# CVSP1_2010.net
KiCad netlist of a schematic drawn in Altium Designer
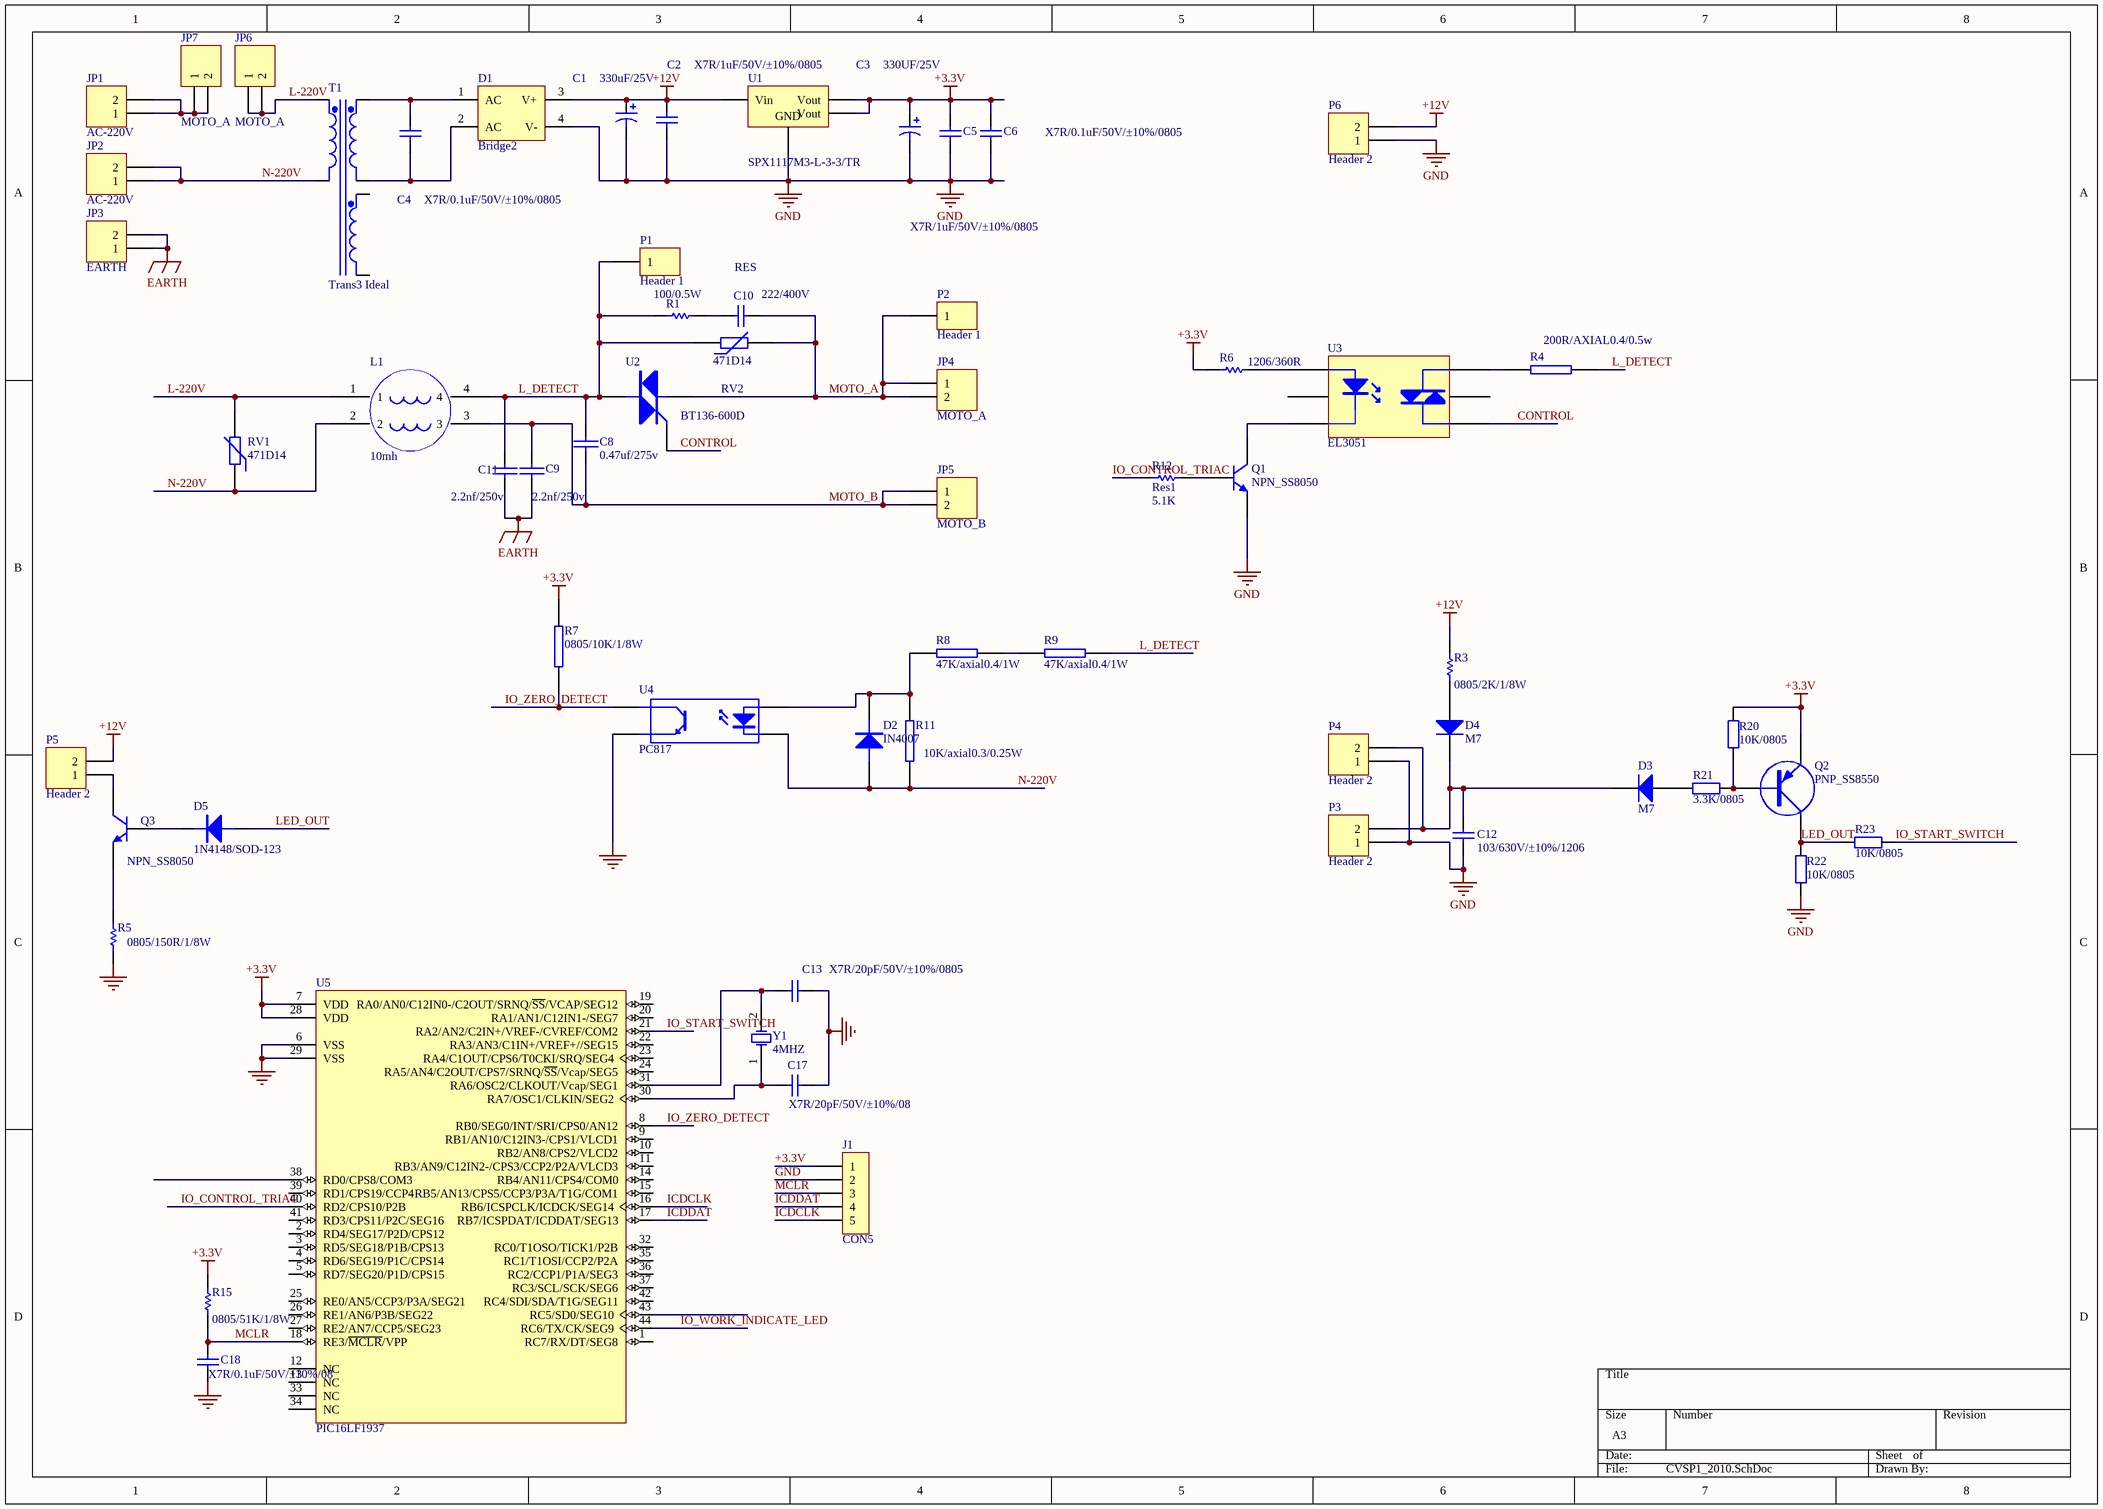
[diagram p0: CVSP1_2010.SchDoc]

(export (version "E")
  (design (tool "Eeschema 10.0.6"))
  (components
    (comp (ref "C1")
      (value "330uF/25V")
      (footprint "CAP/3.2mm*12mm*8mm")
      (description "Polarized Capacitor (Radial)")
      (fields (field (name "Comment") "Cap Pol1") (field (name "PUBLISHER") "Altium Limited"))
      (libsource (lib "Miscellaneous Devices") (part "Cap Pol1"))
    )
    (comp (ref "C2")
      (value "X7R/1uF/50V/±10%/0805")
      (footprint "0805C")
      (description "Capacitor")
      (fields (field (name "Comment") "Cap") (field (name "PUBLISHER") "Altium Limited"))
      (libsource (lib "Miscellaneous Devices") (part "Cap"))
    )
    (comp (ref "C3")
      (value "330UF/25V")
      (footprint "CAP/3.2mm*12mm*8mm")
      (description "Polarized Capacitor (Radial)")
      (fields (field (name "Comment") "Cap Pol1") (field (name "PUBLISHER") "Altium Limited"))
      (libsource (lib "Miscellaneous Devices") (part "Cap Pol1"))
    )
    (comp (ref "C4")
      (value "X7R/0.1uF/50V/±10%/0805")
      (footprint "0805C")
      (description "Capacitor")
      (fields (field (name "PUBLISHER") "Altium Limited"))
      (libsource (lib "Miscellaneous Devices") (part "Cap"))
    )
    (comp (ref "C5")
      (value "X7R/1uF/50V/±10%/0805")
      (footprint "0805C")
      (description "Capacitor")
      (fields (field (name "Comment") "0805/105/25V") (field (name "PUBLISHER") "Altium Limited"))
      (libsource (lib "Miscellaneous Devices") (part "Cap"))
    )
    (comp (ref "C6")
      (value "X7R/0.1uF/50V/±10%/0805")
      (footprint "0805C")
      (description "Capacitor")
      (fields (field (name "PUBLISHER") "Altium Limited"))
      (libsource (lib "Miscellaneous Devices") (part "Cap"))
    )
    (comp (ref "C8")
      (value "0.47uf/275v")
      (footprint "CAP/0.47U/250V")
      (description "Capacitor")
      (libsource (lib "*") (part "CAP"))
    )
    (comp (ref "C9")
      (value "2.2nf/250v")
      (footprint "CAP/1KV")
      (description "Capacitor")
      (libsource (lib "*") (part "CAP"))
    )
    (comp (ref "C10")
      (value "222/400V")
      (footprint "CAP/1KV")
      (description "Capacitor")
      (fields (field (name "Comment") "Cap") (field (name "PUBLISHER") "Altium Limited"))
      (libsource (lib "Miscellaneous Devices") (part "Cap"))
    )
    (comp (ref "C11")
      (value "2.2nf/250v")
      (footprint "CAP/1KV")
      (description "Capacitor")
      (libsource (lib "*") (part "CAP"))
    )
    (comp (ref "C12")
      (value "103/630V/±10%/1206")
      (footprint "0805C")
      (description "Capacitor")
      (fields (field (name "Comment") "Cap") (field (name "PUBLISHER") "Altium Limited"))
      (libsource (lib "Miscellaneous Devices") (part "Cap"))
    )
    (comp (ref "C13")
      (value "X7R/20pF/50V/±10%/0805")
      (footprint "0805C")
      (description "Capacitor")
      (fields (field (name "Comment") "Cap") (field (name "PUBLISHER") "Altium Limited"))
      (libsource (lib "Miscellaneous Devices") (part "Cap"))
    )
    (comp (ref "C17")
      (value "X7R/20pF/50V/±10%/08")
      (footprint "0805C")
      (description "Capacitor")
      (fields (field (name "Comment") "Cap") (field (name "PUBLISHER") "Altium Limited"))
      (libsource (lib "Miscellaneous Devices") (part "Cap"))
    )
    (comp (ref "C18")
      (value "X7R/0.1uF/50V/±10%/08")
      (footprint "0805R")
      (description "Capacitor")
      (fields (field (name "Comment") "0805/104/25V") (field (name "PUBLISHER") "Altium Limited"))
      (libsource (lib "Miscellaneous Devices") (part "Cap"))
    )
    (comp (ref "D1")
      (value "Bridge2")
      (footprint "MB6S(SMT-4)")
      (description "Diode Bridge")
      (fields (field (name "PUBLISHER") "Altium Limited"))
      (libsource (lib "LiHaiMeng") (part "Bridge2"))
    )
    (comp (ref "D2")
      (value "IN4007")
      (footprint "M7")
      (description "Diode")
      (libsource (lib "*") (part "DIODE"))
    )
    (comp (ref "D3")
      (value "M7")
      (footprint "10515.0287_CVSP1_2015_V1.3_2017.04.22_1P:M7")
      (description "1 Amp General Purpose Rectifier")
      (fields (field (name "PUBLISHER") "Altium Limited"))
      (libsource (lib "Miscellaneous Devices") (part "Diode 1N4007"))
    )
    (comp (ref "D4")
      (value "M7")
      (footprint "10515.0287_CVSP1_2015_V1.3_2017.04.22_1P:M7")
      (description "1 Amp General Purpose Rectifier")
      (fields (field (name "PUBLISHER") "Altium Limited"))
      (libsource (lib "Miscellaneous Devices") (part "Diode 1N4007"))
    )
    (comp (ref "D5")
      (value "1N4148/SOD-123")
      (footprint "D/SMT/SOD-123")
      (description "VR=75V T(-65-175)P(0.5W)VF=0.6V")
      (libsource (lib "Menred_原理图 封装库") (part "D/D/SMT/1N4148/SOD-123"))
    )
    (comp (ref "J1")
      (value "CON5")
      (footprint "CON_LCD3")
      (description "Connector")
      (libsource (lib "*") (part "CON5"))
    )
    (comp (ref "JP1")
      (value "AC-220V")
      (footprint "CON-1PIN")
      (description "Header, 2-Pin")
      (fields (field (name "PUBLISHER") "Altium Limited"))
      (libsource (lib "") (part "Header 2_1"))
    )
    (comp (ref "JP2")
      (value "AC-220V")
      (footprint "CON-1PIN")
      (description "Header, 2-Pin")
      (fields (field (name "PUBLISHER") "Altium Limited"))
      (libsource (lib "") (part "Header 2_1"))
    )
    (comp (ref "JP3")
      (value "EARTH")
      (footprint "CON-1PIN")
      (description "Header, 2-Pin")
      (fields (field (name "PUBLISHER") "Altium Limited"))
      (libsource (lib "") (part "Header 2_1"))
    )
    (comp (ref "JP4")
      (value "MOTO_A")
      (footprint "CON-1PIN")
      (description "Header, 2-Pin")
      (fields (field (name "PUBLISHER") "Altium Limited"))
      (libsource (lib "") (part "Header 2_2"))
    )
    (comp (ref "JP5")
      (value "MOTO_B")
      (footprint "CON-1PIN")
      (description "Header, 2-Pin")
      (fields (field (name "PUBLISHER") "Altium Limited"))
      (libsource (lib "") (part "Header 2_2"))
    )
    (comp (ref "JP6")
      (value "MOTO_A")
      (footprint "CON-1PIN")
      (description "Header, 2-Pin")
      (fields (field (name "PUBLISHER") "Altium Limited"))
      (libsource (lib "Miscellaneous Connectors") (part "Header 2"))
    )
    (comp (ref "JP7")
      (value "MOTO_A")
      (footprint "CON-1PIN")
      (description "Header, 2-Pin")
      (fields (field (name "PUBLISHER") "Altium Limited"))
      (libsource (lib "Miscellaneous Connectors") (part "Header 2"))
    )
    (comp (ref "L1") (value "10mh") (footprint "L1") (libsource (lib "LiHaiMeng") (part "INDUCTANCE")))
    (comp (ref "P1")
      (value "Header 1")
      (footprint "CON/1PIN")
      (description "Header, 2-Pin")
      (fields (field (name "PUBLISHER") "Altium Limited"))
      (libsource (lib "LiHaiMeng") (part "Header 1"))
    )
    (comp (ref "P2")
      (value "Header 1")
      (footprint "CON/1PIN")
      (description "Header, 2-Pin")
      (fields (field (name "PUBLISHER") "Altium Limited"))
      (libsource (lib "LiHaiMeng") (part "Header 1"))
    )
    (comp (ref "P3")
      (value "Header 2")
      (footprint "CON-4.0MM*2")
      (description "Header, 2-Pin")
      (fields (field (name "PUBLISHER") "Altium Limited"))
      (libsource (lib "") (part "Header 2_1"))
    )
    (comp (ref "P4")
      (value "Header 2")
      (footprint "CON-4.0MM*2")
      (description "Header, 2-Pin")
      (fields (field (name "PUBLISHER") "Altium Limited"))
      (libsource (lib "") (part "Header 2_1"))
    )
    (comp (ref "P5")
      (value "Header 2")
      (footprint "CON-4.0MM*2")
      (description "Header, 2-Pin")
      (fields (field (name "PUBLISHER") "Altium Limited"))
      (libsource (lib "") (part "Header 2_1"))
    )
    (comp (ref "P6")
      (value "Header 2")
      (footprint "CON-4.0MM*2")
      (description "Header, 2-Pin")
      (fields (field (name "PUBLISHER") "Altium Limited"))
      (libsource (lib "") (part "Header 2_1"))
    )
    (comp (ref "Q1")
      (value "NPN_SS8050")
      (footprint "BJT/SMT/SOT-23")
      (fields (field (name "PUBLISHER") "*"))
      (libsource (lib "Menred_原理图 封装库") (part "BJT/NPN/SMT/SS8050/SOT-23"))
    )
    (comp (ref "Q2")
      (value "PNP_SS8550")
      (footprint "BJT/SMT/SOT-23")
      (description "Vce25V/Vcb40V/Veb5V/Ic1.5V/Pd300mW")
      (libsource (lib "Menred_原理图 封装库") (part "BJT/PNP/SMT/SS8550/SOT-23"))
    )
    (comp (ref "Q3")
      (value "NPN_SS8050")
      (footprint "BJT/SMT/SOT-23")
      (fields (field (name "PUBLISHER") "*"))
      (libsource (lib "Menred_原理图 封装库") (part "BJT/NPN/SMT/SS8050/SOT-23"))
    )
    (comp (ref "R1")
      (value "RES")
      (footprint "R(DIP/0.25W)")
      (description "Resistor")
      (fields (field (name "ALTIUM_VALUE") "100/0.5W") (field (name "PUBLISHER") "Altium Limited"))
      (libsource (lib "Miscellaneous Devices") (part "Res1"))
    )
    (comp (ref "R3")
      (value "0805/2K/1/8W")
      (footprint "0805R")
      (description "Resistor")
      (fields (field (name "Comment") "Res1") (field (name "PUBLISHER") "Altium Limited"))
      (libsource (lib "Miscellaneous Devices") (part "Res1"))
    )
    (comp (ref "R4")
      (value "200R/AXIAL0.4/0.5w")
      (footprint "RDIP/0.4/0.5W")
      (libsource (lib "*") (part "RES2"))
    )
    (comp (ref "R5")
      (value "0805/150R/1/8W")
      (footprint "0805R")
      (description "Resistor")
      (fields (field (name "Comment") "Res1") (field (name "PUBLISHER") "Altium Limited"))
      (libsource (lib "Miscellaneous Devices") (part "Res1"))
    )
    (comp (ref "R6")
      (value "1206/360R")
      (footprint "1206R")
      (description "Resistor")
      (fields (field (name "Comment") "Res1") (field (name "PUBLISHER") "Altium Limited"))
      (libsource (lib "Miscellaneous Devices") (part "Res1"))
    )
    (comp (ref "R7") (value "0805/10K/1/8W") (footprint "0805R") (libsource (lib "*") (part "RES2")))
    (comp (ref "R8") (value "47K/axial0.4/1W") (footprint "0805R") (libsource (lib "*") (part "RES2")))
    (comp (ref "R9") (value "47K/axial0.4/1W") (footprint "R(DIP/0.25W)") (libsource (lib "*") (part "RES2")))
    (comp (ref "R11")
      (value "10K/axial0.3/0.25W")
      (footprint "R[DIP/0.3/0.25W]")
      (libsource (lib "*") (part "RES2"))
    )
    (comp (ref "R12")
      (value "Res1")
      (footprint "0805R")
      (description "Resistor")
      (fields (field (name "ALTIUM_VALUE") "5.1K") (field (name "PUBLISHER") "Altium Limited"))
      (libsource (lib "Miscellaneous Devices") (part "Res1"))
    )
    (comp (ref "R15")
      (value "0805/51K/1/8W")
      (footprint "0805R")
      (description "Resistor")
      (fields (field (name "Comment") "Res1") (field (name "PUBLISHER") "Altium Limited"))
      (libsource (lib "Miscellaneous Devices") (part "Res1"))
    )
    (comp (ref "R20")
      (value "10K/0805")
      (footprint "10515.0287_CVSP1_2015_V1.3_2017.04.22_1P:0805R")
      (description "Resistor")
      (fields (field (name "Comment") "Res2") (field (name "PUBLISHER") "Altium Limited"))
      (libsource (lib "Miscellaneous Devices") (part "Res2"))
    )
    (comp (ref "R21")
      (value "3.3K/0805")
      (footprint "10515.0287_CVSP1_2015_V1.3_2017.04.22_1P:0805R")
      (description "Resistor")
      (fields (field (name "Comment") "Res2") (field (name "PUBLISHER") "Altium Limited"))
      (libsource (lib "") (part "Res2_2"))
    )
    (comp (ref "R22")
      (value "10K/0805")
      (footprint "10515.0287_CVSP1_2015_V1.3_2017.04.22_1P:0805R")
      (description "Resistor")
      (fields (field (name "Comment") "Res2") (field (name "PUBLISHER") "Altium Limited"))
      (libsource (lib "Miscellaneous Devices") (part "Res2"))
    )
    (comp (ref "R23")
      (value "10K/0805")
      (footprint "10515.0287_CVSP1_2015_V1.3_2017.04.22_1P:0805R")
      (description "Resistor")
      (fields (field (name "Comment") "Res2") (field (name "PUBLISHER") "Altium Limited"))
      (libsource (lib "") (part "Res2_1"))
    )
    (comp (ref "RV1")
      (value "471D14")
      (footprint "Menred_原理图 封装库:RES/RY/TDK471KD14")
      (description "Varistor (Voltage-Sensitive Resistor)")
      (fields (field (name "PUBLISHER") "Altium Limited"))
      (libsource (lib "Miscellaneous Devices") (part "Res Varistor"))
    )
    (comp (ref "RV2")
      (value "471D14")
      (footprint "Menred_原理图 封装库:RES/RY/TDK471KD14")
      (description "Varistor (Voltage-Sensitive Resistor)")
      (fields (field (name "PUBLISHER") "Altium Limited"))
      (libsource (lib "Miscellaneous Devices") (part "Res Varistor"))
    )
    (comp (ref "T1")
      (value "Trans3 Ideal")
      (footprint "TRANS1")
      (description "Three-winding Transformer (Ideal)")
      (fields (field (name "PUBLISHER") "Altium Limited"))
      (libsource (lib "Miscellaneous Devices") (part "Trans3 Ideal"))
    )
    (comp (ref "U1")
      (value "SPX1117M3-L-3-3/TR")
      (footprint "SOT-223")
      (description "Voltage Regulator")
      (fields (field (name "PUBLISHER") "Altium Limited"))
      (libsource (lib "LiHaiMeng") (part "SPX3117"))
    )
    (comp (ref "U2") (value "BT136-600D") (footprint "BTA41_800B") (libsource (lib "*") (part "TRIAC")))
    (comp (ref "U3")
      (value "EL3051")
      (footprint "MOC3052(DIP-6)")
      (libsource (lib "LiHaiMeng") (part "MOC3043"))
    )
    (comp (ref "U4")
      (value "PC817")
      (footprint "PC817(DIP-4)")
      (description "Optoisolator")
      (libsource (lib "*") (part "OPTOISO1"))
    )
    (comp (ref "U5")
      (value "PIC16LF1937")
      (footprint "TQFP44")
      (fields (field (name "PUBLISHER") "Altium Limited"))
      (libsource (lib "LiHaiMeng") (part "PIC16LF1937"))
    )
    (comp (ref "Y1")
      (value "4MHZ")
      (footprint "Y1(DIP-5.08mm)")
      (description "Crystal Oscillator")
      (fields (field (name "PUBLISHER") "Altium Limited"))
      (libsource (lib "Miscellaneous Devices") (part "XTAL"))
    )
  )
  (nets
    (net (code "1") (name "+3.3V") (class "Default")
      (node (ref "C3") (pin "1") (pinfunction "1_1") (pintype "passive"))
      (node (ref "C5") (pin "2") (pinfunction "2_2") (pintype "passive"))
      (node (ref "C6") (pin "2") (pinfunction "2_2") (pintype "passive"))
      (node (ref "J1") (pin "1") (pinfunction "1_1") (pintype "passive"))
      (node (ref "Q2") (pin "2") (pinfunction "E_2") (pintype "passive"))
      (node (ref "R15") (pin "2") (pinfunction "2_2") (pintype "passive"))
      (node (ref "R20") (pin "2") (pinfunction "2_2") (pintype "passive"))
      (node (ref "R6") (pin "1") (pinfunction "1_1") (pintype "passive"))
      (node (ref "R7") (pin "2") (pinfunction "2_2") (pintype "passive"))
      (node (ref "U1") (pin "2") (pinfunction "Vout_2") (pintype "passive"))
      (node (ref "U1") (pin "4") (pinfunction "Vout_4") (pintype "passive"))
      (node (ref "U5") (pin "28") (pinfunction "VDD_28") (pintype "power_in"))
      (node (ref "U5") (pin "7") (pinfunction "VDD_7") (pintype "power_in"))
    )
    (net (code "2") (name "+12V") (class "Default")
      (node (ref "C1") (pin "1") (pinfunction "1_1") (pintype "passive"))
      (node (ref "C2") (pin "2") (pinfunction "2_2") (pintype "passive"))
      (node (ref "D1") (pin "3") (pinfunction "V+_3") (pintype "passive"))
      (node (ref "P5") (pin "2") (pinfunction "2_2") (pintype "passive"))
      (node (ref "P6") (pin "2") (pinfunction "2_2") (pintype "passive"))
      (node (ref "R3") (pin "2") (pinfunction "2_2") (pintype "passive"))
      (node (ref "U1") (pin "3") (pinfunction "Vin_3") (pintype "passive"))
    )
    (net (code "3") (name "/CONTROL") (class "Default")
      (node (ref "U2") (pin "3") (pinfunction "G_3") (pintype "passive"))
      (node (ref "U3") (pin "4") (pinfunction "4_4") (pintype "passive"))
    )
    (net (code "4") (name "/ICDCLK") (class "Default")
      (node (ref "J1") (pin "5") (pinfunction "5_5") (pintype "passive"))
      (node (ref "U5") (pin "16") (pinfunction "RB6/ICSPCLK/ICDCK/SEG14_16") (pintype "bidirectional"))
    )
    (net (code "5") (name "/ICDDAT") (class "Default")
      (node (ref "J1") (pin "4") (pinfunction "4_4") (pintype "passive"))
      (node (ref "U5") (pin "17") (pinfunction "RB7/ICSPDAT/ICDDAT/SEG13_17") (pintype "bidirectional"))
    )
    (net (code "6") (name "/IO_CONTROL_TRIAC") (class "Default")
      (node (ref "R12") (pin "1") (pinfunction "1_1") (pintype "passive"))
      (node (ref "U5") (pin "40") (pinfunction "RD2/CPS10/P2B_40") (pintype "bidirectional"))
    )
    (net (code "7") (name "/IO_START_SWITCH") (class "Default")
      (node (ref "R23") (pin "1") (pinfunction "1_1") (pintype "passive"))
      (node (ref "U5") (pin "21") (pinfunction "RA2/AN2/C2IN+/VREF-/CVREF/COM2_21") (pintype "bidirectional"))
    )
    (net (code "8") (name "/IO_WORK_INDICATE_LED") (class "Default")
      (node (ref "U5") (pin "44") (pinfunction "RC6/TX/CK/SEG9_44") (pintype "bidirectional"))
    )
    (net (code "9") (name "/IO_ZERO_DETECT") (class "Default")
      (node (ref "R7") (pin "1") (pinfunction "1_1") (pintype "passive"))
      (node (ref "U4") (pin "4") (pinfunction "C_4") (pintype "passive"))
      (node (ref "U5") (pin "8") (pinfunction "RB0/SEG0/INT/SRI/CPS0/AN12_8") (pintype "bidirectional"))
    )
    (net (code "10") (name "/L-220V") (class "Default")
      (node (ref "JP6") (pin "1") (pinfunction "1_1") (pintype "passive"))
      (node (ref "JP6") (pin "2") (pinfunction "2_2") (pintype "passive"))
      (node (ref "L1") (pin "1") (pinfunction "1_1") (pintype "passive"))
      (node (ref "RV1") (pin "2") (pinfunction "2_2") (pintype "passive"))
      (node (ref "T1") (pin "1") (pinfunction "Pri+_1") (pintype "passive"))
    )
    (net (code "11") (name "/LED_OUT") (class "Default")
      (node (ref "D5") (pin "2") (pinfunction "A_2") (pintype "passive"))
      (node (ref "Q2") (pin "3") (pinfunction "C_3") (pintype "passive"))
      (node (ref "R22") (pin "2") (pinfunction "2_2") (pintype "passive"))
      (node (ref "R23") (pin "2") (pinfunction "2_2") (pintype "passive"))
    )
    (net (code "12") (name "/L_DETECT") (class "Default")
      (node (ref "C11") (pin "2") (pinfunction "2_2") (pintype "passive"))
      (node (ref "C8") (pin "2") (pinfunction "2_2") (pintype "passive"))
      (node (ref "L1") (pin "4") (pinfunction "4_4") (pintype "passive"))
      (node (ref "P1") (pin "1") (pinfunction "1_1") (pintype "passive"))
      (node (ref "R1") (pin "1") (pinfunction "1_1") (pintype "passive"))
      (node (ref "R4") (pin "2") (pinfunction "2_2") (pintype "passive"))
      (node (ref "R9") (pin "1") (pinfunction "1_1") (pintype "passive"))
      (node (ref "RV2") (pin "1") (pinfunction "1_1") (pintype "passive"))
      (node (ref "U2") (pin "2") (pinfunction "T_2") (pintype "passive"))
    )
    (net (code "13") (name "/MCLR") (class "Default")
      (node (ref "C18") (pin "2") (pinfunction "2_2") (pintype "passive"))
      (node (ref "J1") (pin "3") (pinfunction "3_3") (pintype "passive"))
      (node (ref "R15") (pin "1") (pinfunction "1_1") (pintype "passive"))
      (node (ref "U5") (pin "18") (pinfunction "RE3/~{MCLR}/VPP_18") (pintype "bidirectional"))
    )
    (net (code "14") (name "/MOTO_A") (class "Default")
      (node (ref "C10") (pin "1") (pinfunction "1_1") (pintype "passive"))
      (node (ref "JP4") (pin "1") (pinfunction "1_1") (pintype "passive"))
      (node (ref "JP4") (pin "2") (pinfunction "2_2") (pintype "passive"))
      (node (ref "P2") (pin "1") (pinfunction "1_1") (pintype "passive"))
      (node (ref "RV2") (pin "2") (pinfunction "2_2") (pintype "passive"))
      (node (ref "U2") (pin "1") (pinfunction "T_1") (pintype "passive"))
    )
    (net (code "15") (name "/MOTO_B") (class "Default")
      (node (ref "C8") (pin "1") (pinfunction "1_1") (pintype "passive"))
      (node (ref "C9") (pin "2") (pinfunction "2_2") (pintype "passive"))
      (node (ref "JP5") (pin "1") (pinfunction "1_1") (pintype "passive"))
      (node (ref "JP5") (pin "2") (pinfunction "2_2") (pintype "passive"))
      (node (ref "L1") (pin "3") (pinfunction "3_3") (pintype "passive"))
    )
    (net (code "16") (name "/N-220V") (class "Default")
      (node (ref "D2") (pin "1") (pinfunction "A_1") (pintype "passive"))
      (node (ref "JP2") (pin "1") (pinfunction "1_1") (pintype "passive"))
      (node (ref "JP2") (pin "2") (pinfunction "2_2") (pintype "passive"))
      (node (ref "L1") (pin "2") (pinfunction "2_2") (pintype "passive"))
      (node (ref "R11") (pin "1") (pinfunction "1_1") (pintype "passive"))
      (node (ref "RV1") (pin "1") (pinfunction "1_1") (pintype "passive"))
      (node (ref "T1") (pin "2") (pinfunction "Pri-_2") (pintype "passive"))
      (node (ref "U4") (pin "2") (pinfunction "K_2") (pintype "passive"))
    )
    (net (code "17") (name "EARTH") (class "Default")
      (node (ref "C11") (pin "1") (pinfunction "1_1") (pintype "passive"))
      (node (ref "C9") (pin "1") (pinfunction "1_1") (pintype "passive"))
      (node (ref "JP3") (pin "1") (pinfunction "1_1") (pintype "passive"))
      (node (ref "JP3") (pin "2") (pinfunction "2_2") (pintype "passive"))
    )
    (net (code "18") (name "GND") (class "Default")
      (node (ref "C1") (pin "2") (pinfunction "2_2") (pintype "passive"))
      (node (ref "C12") (pin "1") (pinfunction "1_1") (pintype "passive"))
      (node (ref "C13") (pin "1") (pinfunction "1_1") (pintype "passive"))
      (node (ref "C17") (pin "1") (pinfunction "1_1") (pintype "passive"))
      (node (ref "C18") (pin "1") (pinfunction "1_1") (pintype "passive"))
      (node (ref "C2") (pin "1") (pinfunction "1_1") (pintype "passive"))
      (node (ref "C3") (pin "2") (pinfunction "2_2") (pintype "passive"))
      (node (ref "C5") (pin "1") (pinfunction "1_1") (pintype "passive"))
      (node (ref "C6") (pin "1") (pinfunction "1_1") (pintype "passive"))
      (node (ref "D1") (pin "4") (pinfunction "V-_4") (pintype "passive"))
      (node (ref "J1") (pin "2") (pinfunction "2_2") (pintype "passive"))
      (node (ref "P3") (pin "1") (pinfunction "1_1") (pintype "passive"))
      (node (ref "P4") (pin "1") (pinfunction "1_1") (pintype "passive"))
      (node (ref "P6") (pin "1") (pinfunction "1_1") (pintype "passive"))
      (node (ref "Q1") (pin "2") (pinfunction "E_2") (pintype "passive"))
      (node (ref "R22") (pin "1") (pinfunction "1_1") (pintype "passive"))
      (node (ref "R5") (pin "1") (pinfunction "1_1") (pintype "passive"))
      (node (ref "U1") (pin "1") (pinfunction "GND_1") (pintype "passive"))
      (node (ref "U4") (pin "3") (pinfunction "E_3") (pintype "passive"))
      (node (ref "U5") (pin "29") (pinfunction "VSS_29") (pintype "power_in"))
      (node (ref "U5") (pin "6") (pinfunction "VSS_6") (pintype "power_in"))
    )
    (net (code "19") (name "Net-(C10-Pad2)") (class "Default")
      (node (ref "C10") (pin "2") (pinfunction "2_2") (pintype "passive"))
      (node (ref "R1") (pin "2") (pinfunction "2_2") (pintype "passive"))
    )
    (net (code "20") (name "Net-(D2-K)") (class "Default")
      (node (ref "D2") (pin "2") (pinfunction "K_2") (pintype "passive"))
      (node (ref "R11") (pin "2") (pinfunction "2_2") (pintype "passive"))
      (node (ref "R8") (pin "2") (pinfunction "2_2") (pintype "passive"))
      (node (ref "U4") (pin "1") (pinfunction "A_1") (pintype "passive"))
    )
    (net (code "21") (name "Net-(D3-A)") (class "Default")
      (node (ref "D3") (pin "1") (pinfunction "A_1") (pintype "passive"))
      (node (ref "R21") (pin "1") (pinfunction "1_1") (pintype "passive"))
    )
    (net (code "22") (name "Net-(D3-K)") (class "Default")
      (node (ref "C12") (pin "2") (pinfunction "2_2") (pintype "passive"))
      (node (ref "D3") (pin "2") (pinfunction "K_2") (pintype "passive"))
      (node (ref "D4") (pin "2") (pinfunction "K_2") (pintype "passive"))
      (node (ref "P3") (pin "2") (pinfunction "2_2") (pintype "passive"))
      (node (ref "P4") (pin "2") (pinfunction "2_2") (pintype "passive"))
    )
    (net (code "23") (name "Net-(D4-A)") (class "Default")
      (node (ref "D4") (pin "1") (pinfunction "A_1") (pintype "passive"))
      (node (ref "R3") (pin "1") (pinfunction "1_1") (pintype "passive"))
    )
    (net (code "24") (name "Net-(D5-K)") (class "Default")
      (node (ref "D5") (pin "1") (pinfunction "K_1") (pintype "passive"))
      (node (ref "Q3") (pin "1") (pinfunction "B_1") (pintype "passive"))
    )
    (net (code "25") (name "Net-(JP1-Pad1)") (class "Default")
      (node (ref "JP1") (pin "1") (pinfunction "1_1") (pintype "passive"))
      (node (ref "JP1") (pin "2") (pinfunction "2_2") (pintype "passive"))
      (node (ref "JP7") (pin "1") (pinfunction "1_1") (pintype "passive"))
      (node (ref "JP7") (pin "2") (pinfunction "2_2") (pintype "passive"))
    )
    (net (code "26") (name "Net-(Q1-B)") (class "Default")
      (node (ref "Q1") (pin "1") (pinfunction "B_1") (pintype "passive"))
      (node (ref "R12") (pin "2") (pinfunction "2_2") (pintype "passive"))
    )
    (net (code "27") (name "Net-(Q1-C)") (class "Default")
      (node (ref "Q1") (pin "3") (pinfunction "C_3") (pintype "passive"))
      (node (ref "U3") (pin "2") (pinfunction "2_2") (pintype "passive"))
    )
    (net (code "28") (name "Net-(Q2-B)") (class "Default")
      (node (ref "Q2") (pin "1") (pinfunction "B_1") (pintype "passive"))
      (node (ref "R20") (pin "1") (pinfunction "1_1") (pintype "passive"))
      (node (ref "R21") (pin "2") (pinfunction "2_2") (pintype "passive"))
    )
    (net (code "29") (name "Net-(Q3-C)") (class "Default")
      (node (ref "P5") (pin "1") (pinfunction "1_1") (pintype "passive"))
      (node (ref "Q3") (pin "3") (pinfunction "C_3") (pintype "passive"))
    )
    (net (code "30") (name "Net-(Q3-E)") (class "Default")
      (node (ref "Q3") (pin "2") (pinfunction "E_2") (pintype "passive"))
      (node (ref "R5") (pin "2") (pinfunction "2_2") (pintype "passive"))
    )
    (net (code "31") (name "Net-(R4-Pad1)") (class "Default")
      (node (ref "R4") (pin "1") (pinfunction "1_1") (pintype "passive"))
      (node (ref "U3") (pin "6") (pinfunction "6_6") (pintype "passive"))
    )
    (net (code "32") (name "Net-(R6-Pad2)") (class "Default")
      (node (ref "R6") (pin "2") (pinfunction "2_2") (pintype "passive"))
      (node (ref "U3") (pin "1") (pinfunction "1_1") (pintype "passive"))
    )
    (net (code "33") (name "Net-(R8-Pad1)") (class "Default")
      (node (ref "R8") (pin "1") (pinfunction "1_1") (pintype "passive"))
      (node (ref "R9") (pin "2") (pinfunction "2_2") (pintype "passive"))
    )
    (net (code "34") (name "Net-(T1-Sec1+)") (class "Default")
      (node (ref "C4") (pin "2") (pinfunction "2_2") (pintype "passive"))
      (node (ref "D1") (pin "1") (pinfunction "AC_1") (pintype "passive"))
      (node (ref "T1") (pin "3") (pinfunction "Sec1+_3") (pintype "passive"))
    )
    (net (code "35") (name "Net-(T1-Sec1-)") (class "Default")
      (node (ref "C4") (pin "1") (pinfunction "1_1") (pintype "passive"))
      (node (ref "D1") (pin "2") (pinfunction "AC_2") (pintype "passive"))
      (node (ref "T1") (pin "4") (pinfunction "Sec1-_4") (pintype "passive"))
    )
    (net (code "36") (name "Net-(U5-RA6{slash}OSC2{slash}CLKOUT{slash}Vcap{slash}SEG1)") (class "Default")
      (node (ref "C13") (pin "2") (pinfunction "2_2") (pintype "passive"))
      (node (ref "U5") (pin "31") (pinfunction "RA6/OSC2/CLKOUT/Vcap/SEG1_31") (pintype "bidirectional"))
      (node (ref "Y1") (pin "2") (pinfunction "OSC2_2") (pintype "passive"))
    )
    (net (code "37") (name "Net-(U5-RA7{slash}OSC1{slash}CLKIN{slash}SEG2)") (class "Default")
      (node (ref "C17") (pin "2") (pinfunction "2_2") (pintype "passive"))
      (node (ref "U5") (pin "30") (pinfunction "RA7/OSC1/CLKIN/SEG2_30") (pintype "bidirectional"))
      (node (ref "Y1") (pin "1") (pinfunction "OSC1_1") (pintype "passive"))
    )
    (net (code "38") (name "unconnected-(T1-Sec2+-Pad5)") (class "Default")
      (node (ref "T1") (pin "5") (pinfunction "Sec2+_5") (pintype "passive"))
    )
    (net (code "39") (name "unconnected-(T1-Sec2--Pad6)") (class "Default")
      (node (ref "T1") (pin "6") (pinfunction "Sec2-_6") (pintype "passive"))
    )
    (net (code "40") (name "unconnected-(U3-Pad3)") (class "Default")
      (node (ref "U3") (pin "3") (pinfunction "3_3") (pintype "passive"))
    )
    (net (code "41") (name "unconnected-(U3-Pad5)") (class "Default")
      (node (ref "U3") (pin "5") (pinfunction "5_5") (pintype "passive"))
    )
    (net (code "42") (name "unconnected-(U5-NC-Pad12)") (class "Default")
      (node (ref "U5") (pin "12") (pinfunction "NC_12") (pintype "passive"))
    )
    (net (code "43") (name "unconnected-(U5-NC-Pad13)") (class "Default")
      (node (ref "U5") (pin "13") (pinfunction "NC_13") (pintype "passive"))
    )
    (net (code "44") (name "unconnected-(U5-NC-Pad33)") (class "Default")
      (node (ref "U5") (pin "33") (pinfunction "NC_33") (pintype "passive"))
    )
    (net (code "45") (name "unconnected-(U5-NC-Pad34)") (class "Default")
      (node (ref "U5") (pin "34") (pinfunction "NC_34") (pintype "passive"))
    )
    (net (code "46") (name "unconnected-(U5-RA0{slash}AN0{slash}C12IN0-{slash}C2OUT{slash}SRNQ{slash}~{SS}{slash}VCAP{slash}SEG12-Pad19)") (class "Default")
      (node (ref "U5") (pin "19") (pinfunction "RA0/AN0/C12IN0-/C2OUT/SRNQ/~{SS}/VCAP/SEG12_19") (pintype "bidirectional"))
    )
    (net (code "47") (name "unconnected-(U5-RA1{slash}AN1{slash}C12IN1-{slash}SEG7-Pad20)") (class "Default")
      (node (ref "U5") (pin "20") (pinfunction "RA1/AN1/C12IN1-/SEG7_20") (pintype "bidirectional"))
    )
    (net (code "48") (name "unconnected-(U5-RA3{slash}AN3{slash}C1IN+{slash}VREF+{slash}{slash}SEG15-Pad22)") (class "Default")
      (node (ref "U5") (pin "22") (pinfunction "RA3/AN3/C1IN+/VREF+//SEG15_22") (pintype "bidirectional"))
    )
    (net (code "49") (name "unconnected-(U5-RA4{slash}C1OUT{slash}CPS6{slash}T0CKI{slash}SRQ{slash}SEG4-Pad23)") (class "Default")
      (node (ref "U5") (pin "23") (pinfunction "RA4/C1OUT/CPS6/T0CKI/SRQ/SEG4_23") (pintype "bidirectional"))
    )
    (net (code "50") (name "unconnected-(U5-RA5{slash}AN4{slash}C2OUT{slash}CPS7{slash}SRNQ{slash}~{SS}{slash}Vcap{slash}SEG5-Pad24)") (class "Default")
      (node (ref "U5") (pin "24") (pinfunction "RA5/AN4/C2OUT/CPS7/SRNQ/~{SS}/Vcap/SEG5_24") (pintype "bidirectional"))
    )
    (net (code "51") (name "unconnected-(U5-RB1{slash}AN10{slash}C12IN3-{slash}CPS1{slash}VLCD1-Pad9)") (class "Default")
      (node (ref "U5") (pin "9") (pinfunction "RB1/AN10/C12IN3-/CPS1/VLCD1_9") (pintype "bidirectional"))
    )
    (net (code "52") (name "unconnected-(U5-RB2{slash}AN8{slash}CPS2{slash}VLCD2-Pad10)") (class "Default")
      (node (ref "U5") (pin "10") (pinfunction "RB2/AN8/CPS2/VLCD2_10") (pintype "bidirectional"))
    )
    (net (code "53") (name "unconnected-(U5-RB3{slash}AN9{slash}C12IN2-{slash}CPS3{slash}CCP2{slash}P2A{slash}VLCD3-Pad11)") (class "Default")
      (node (ref "U5") (pin "11") (pinfunction "RB3/AN9/C12IN2-/CPS3/CCP2/P2A/VLCD3_11") (pintype "bidirectional"))
    )
    (net (code "54") (name "unconnected-(U5-RB4{slash}AN11{slash}CPS4{slash}COM0-Pad14)") (class "Default")
      (node (ref "U5") (pin "14") (pinfunction "RB4/AN11/CPS4/COM0_14") (pintype "bidirectional"))
    )
    (net (code "55") (name "unconnected-(U5-RB5{slash}AN13{slash}CPS5{slash}CCP3{slash}P3A{slash}T1G{slash}COM1-Pad15)") (class "Default")
      (node (ref "U5") (pin "15") (pinfunction "RB5/AN13/CPS5/CCP3/P3A/T1G/COM1_15") (pintype "bidirectional"))
    )
    (net (code "56") (name "unconnected-(U5-RC0{slash}T1OSO{slash}TICK1{slash}P2B-Pad32)") (class "Default")
      (node (ref "U5") (pin "32") (pinfunction "RC0/T1OSO/TICK1/P2B_32") (pintype "bidirectional"))
    )
    (net (code "57") (name "unconnected-(U5-RC1{slash}T1OSI{slash}CCP2{slash}P2A-Pad35)") (class "Default")
      (node (ref "U5") (pin "35") (pinfunction "RC1/T1OSI/CCP2/P2A_35") (pintype "bidirectional"))
    )
    (net (code "58") (name "unconnected-(U5-RC2{slash}CCP1{slash}P1A{slash}SEG3-Pad36)") (class "Default")
      (node (ref "U5") (pin "36") (pinfunction "RC2/CCP1/P1A/SEG3_36") (pintype "bidirectional"))
    )
    (net (code "59") (name "unconnected-(U5-RC3{slash}SCL{slash}SCK{slash}SEG6-Pad37)") (class "Default")
      (node (ref "U5") (pin "37") (pinfunction "RC3/SCL/SCK/SEG6_37") (pintype "bidirectional"))
    )
    (net (code "60") (name "unconnected-(U5-RC4{slash}SDI{slash}SDA{slash}T1G{slash}SEG11-Pad42)") (class "Default")
      (node (ref "U5") (pin "42") (pinfunction "RC4/SDI/SDA/T1G/SEG11_42") (pintype "bidirectional"))
    )
    (net (code "61") (name "unconnected-(U5-RC5{slash}SD0{slash}SEG10-Pad43)") (class "Default")
      (node (ref "U5") (pin "43") (pinfunction "RC5/SD0/SEG10_43") (pintype "bidirectional"))
    )
    (net (code "62") (name "unconnected-(U5-RC7{slash}RX{slash}DT{slash}SEG8-Pad1)") (class "Default")
      (node (ref "U5") (pin "1") (pinfunction "RC7/RX/DT/SEG8_1") (pintype "bidirectional"))
    )
    (net (code "63") (name "unconnected-(U5-RD0{slash}CPS8{slash}COM3-Pad38)") (class "Default")
      (node (ref "U5") (pin "38") (pinfunction "RD0/CPS8/COM3_38") (pintype "bidirectional"))
    )
    (net (code "64") (name "unconnected-(U5-RD1{slash}CPS19{slash}CCP4-Pad39)") (class "Default")
      (node (ref "U5") (pin "39") (pinfunction "RD1/CPS19/CCP4_39") (pintype "bidirectional"))
    )
    (net (code "65") (name "unconnected-(U5-RD3{slash}CPS11{slash}P2C{slash}SEG16-Pad41)") (class "Default")
      (node (ref "U5") (pin "41") (pinfunction "RD3/CPS11/P2C/SEG16_41") (pintype "bidirectional"))
    )
    (net (code "66") (name "unconnected-(U5-RD4{slash}SEG17{slash}P2D{slash}CPS12-Pad2)") (class "Default")
      (node (ref "U5") (pin "2") (pinfunction "RD4/SEG17/P2D/CPS12_2") (pintype "bidirectional"))
    )
    (net (code "67") (name "unconnected-(U5-RD5{slash}SEG18{slash}P1B{slash}CPS13-Pad3)") (class "Default")
      (node (ref "U5") (pin "3") (pinfunction "RD5/SEG18/P1B/CPS13_3") (pintype "bidirectional"))
    )
    (net (code "68") (name "unconnected-(U5-RD6{slash}SEG19{slash}P1C{slash}CPS14-Pad4)") (class "Default")
      (node (ref "U5") (pin "4") (pinfunction "RD6/SEG19/P1C/CPS14_4") (pintype "bidirectional"))
    )
    (net (code "69") (name "unconnected-(U5-RD7{slash}SEG20{slash}P1D{slash}CPS15-Pad5)") (class "Default")
      (node (ref "U5") (pin "5") (pinfunction "RD7/SEG20/P1D/CPS15_5") (pintype "bidirectional"))
    )
    (net (code "70") (name "unconnected-(U5-RE0{slash}AN5{slash}CCP3{slash}P3A{slash}SEG21-Pad25)") (class "Default")
      (node (ref "U5") (pin "25") (pinfunction "RE0/AN5/CCP3/P3A/SEG21_25") (pintype "bidirectional"))
    )
    (net (code "71") (name "unconnected-(U5-RE1{slash}AN6{slash}P3B{slash}SEG22-Pad26)") (class "Default")
      (node (ref "U5") (pin "26") (pinfunction "RE1/AN6/P3B/SEG22_26") (pintype "bidirectional"))
    )
    (net (code "72") (name "unconnected-(U5-RE2{slash}AN7{slash}CCP5{slash}SEG23-Pad27)") (class "Default")
      (node (ref "U5") (pin "27") (pinfunction "RE2/AN7/CCP5/SEG23_27") (pintype "bidirectional"))
    )
  )
)
